# Door.net
KiCad netlist of a schematic drawn in Altium Designer
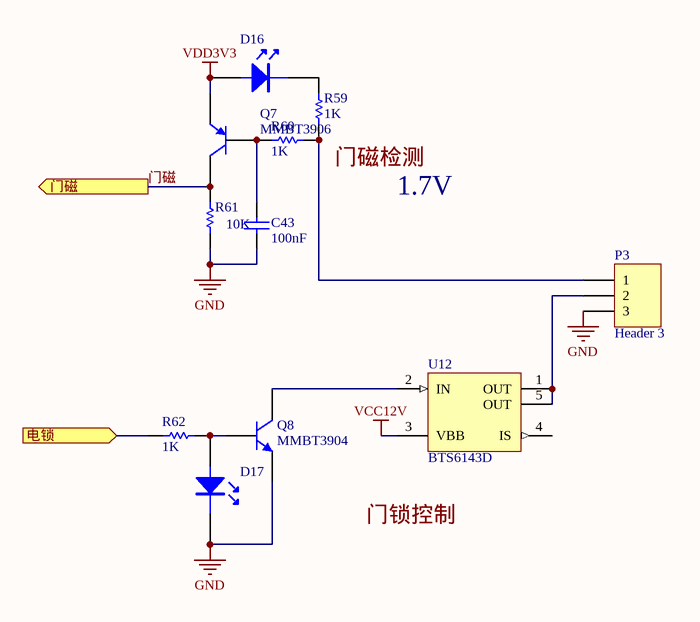
[diagram p0: Door.SchDoc]

(export (version "E")
  (design (tool "Eeschema 10.0.6"))
  (components
    (comp (ref "C43")
      (value "100nF")
      (footprint "CAPC0805(2012)100_L")
      (description "CAP 100nF 50V ±5% 0805 (2012 Metric) Thickness 1mm SMD")
      (fields (field (name "TOLERANCE") "±5%") (field (name "Comment") "CAP 100nF 50V 0805(2012)"))
      (libsource (lib "Altium Content Vault") (part "CMP-1036-04418-1"))
    )
    (comp (ref "D16") (value "~") (footprint "0805-L") (libsource (lib "*") (part "LED")))
    (comp (ref "D17") (value "~") (footprint "0805-L") (libsource (lib "*") (part "LED")))
    (comp (ref "P3")
      (value "Header 3")
      (footprint "HDR1X3")
      (description "Header, 3-Pin")
      (fields (field (name "PUBLISHER") "Altium Limited"))
      (libsource (lib "Miscellaneous Connectors") (part "Header 3"))
    )
    (comp (ref "Q7")
      (value "MMBT3906")
      (footprint "SOT23_N")
      (description "PNP Switching Transistor")
      (fields (field (name "PUBLISHER") "Altium Limited"))
      (libsource (lib "Philips Discrete BJT - Low Power") (part "MMBT3906"))
    )
    (comp (ref "Q8")
      (value "MMBT3904")
      (footprint "SOT23_N")
      (description "NPN Switching Transistor")
      (fields (field (name "PUBLISHER") "Altium Limited"))
      (libsource (lib "Philips Discrete BJT - Low Power") (part "MMBT3904"))
    )
    (comp (ref "R59")
      (value "1K")
      (footprint "RESC0805(2012)_M")
      (description "1K 0.125W 1% 0805 (2012 Metric)  SMD")
      (fields (field (name "TOLERANCE") "1 %") (field (name "POWER") "0.125 W"))
      (libsource (lib "Altium Content Vault") (part "CMP-1013-00510-1"))
    )
    (comp (ref "R60")
      (value "1K")
      (footprint "RESC0805(2012)_M")
      (description "1K 0.125W 1% 0805 (2012 Metric)  SMD")
      (fields (field (name "TOLERANCE") "1 %") (field (name "POWER") "0.125 W"))
      (libsource (lib "Altium Content Vault") (part "CMP-1013-00510-1"))
    )
    (comp (ref "R61")
      (value "10K")
      (footprint "RESC0805(2012)_M")
      (description "10K 0.125W 1% 0805 (2012 Metric)  SMD")
      (fields (field (name "TOLERANCE") "1 %") (field (name "POWER") "0.125 W"))
      (libsource (lib "Altium Content Vault") (part "CMP-1013-00623-1"))
    )
    (comp (ref "R62")
      (value "1K")
      (footprint "RESC0805(2012)_M")
      (description "1K 0.125W 1% 0805 (2012 Metric)  SMD")
      (fields (field (name "TOLERANCE") "1 %") (field (name "POWER") "0.125 W"))
      (libsource (lib "Altium Content Vault") (part "CMP-1013-00510-1"))
    )
    (comp (ref "U12")
      (value "BTS6143D")
      (footprint "INF-PG-TO252-5-11_N")
      (fields (field (name "MANUFACTURER") "Infineon"))
      (libsource (lib "Altium Content Vault") (part "INF-BTS61XXD-PG-TO252-5-11-5"))
    )
  )
  (nets
    (net (code "1") (name "/电锁") (class "Default")
      (node (ref "R62") (pin "2") (pinfunction "2_2") (pintype "passive"))
    )
    (net (code "2") (name "/门磁") (class "Default")
      (node (ref "Q7") (pin "3") (pinfunction "C_3") (pintype "passive"))
      (node (ref "R61") (pin "2") (pinfunction "2_2") (pintype "passive"))
    )
    (net (code "3") (name "GND") (class "Default")
      (node (ref "C43") (pin "1") (pinfunction "1_1") (pintype "passive"))
      (node (ref "D17") (pin "2") (pinfunction "2_2") (pintype "passive"))
      (node (ref "P3") (pin "3") (pinfunction "3_3") (pintype "passive"))
      (node (ref "Q8") (pin "2") (pinfunction "E_2") (pintype "passive"))
      (node (ref "R61") (pin "1") (pinfunction "1_1") (pintype "passive"))
    )
    (net (code "4") (name "Net-(D16-Pad2)") (class "Default")
      (node (ref "D16") (pin "2") (pinfunction "2_2") (pintype "passive"))
      (node (ref "R59") (pin "2") (pinfunction "2_2") (pintype "passive"))
    )
    (net (code "5") (name "Net-(P3-Pad1)") (class "Default")
      (node (ref "P3") (pin "1") (pinfunction "1_1") (pintype "passive"))
      (node (ref "R59") (pin "1") (pinfunction "1_1") (pintype "passive"))
      (node (ref "R60") (pin "2") (pinfunction "2_2") (pintype "passive"))
    )
    (net (code "6") (name "Net-(P3-Pad2)") (class "Default")
      (node (ref "P3") (pin "2") (pinfunction "2_2") (pintype "passive"))
      (node (ref "U12") (pin "1") (pinfunction "OUT_1") (pintype "tri_state"))
      (node (ref "U12") (pin "5") (pinfunction "OUT_5") (pintype "tri_state"))
    )
    (net (code "7") (name "Net-(Q7-B)") (class "Default")
      (node (ref "C43") (pin "2") (pinfunction "2_2") (pintype "passive"))
      (node (ref "Q7") (pin "1") (pinfunction "B_1") (pintype "passive"))
      (node (ref "R60") (pin "1") (pinfunction "1_1") (pintype "passive"))
    )
    (net (code "8") (name "Net-(Q8-B)") (class "Default")
      (node (ref "D17") (pin "1") (pinfunction "1_1") (pintype "passive"))
      (node (ref "Q8") (pin "1") (pinfunction "B_1") (pintype "passive"))
      (node (ref "R62") (pin "1") (pinfunction "1_1") (pintype "passive"))
    )
    (net (code "9") (name "Net-(Q8-C)") (class "Default")
      (node (ref "Q8") (pin "3") (pinfunction "C_3") (pintype "passive"))
      (node (ref "U12") (pin "2") (pinfunction "IN_2") (pintype "input"))
    )
    (net (code "10") (name "VCC12V") (class "Default")
      (node (ref "U12") (pin "3") (pinfunction "VBB_3") (pintype "power_in"))
    )
    (net (code "11") (name "VDD3V3") (class "Default")
      (node (ref "D16") (pin "1") (pinfunction "1_1") (pintype "passive"))
      (node (ref "Q7") (pin "2") (pinfunction "E_2") (pintype "passive"))
    )
    (net (code "12") (name "unconnected-(U12-IS-Pad4)") (class "Default")
      (node (ref "U12") (pin "4") (pinfunction "IS_4") (pintype "output"))
    )
  )
)
